# daisy-remote.net
KiCad netlist of a schematic drawn in EAGLE
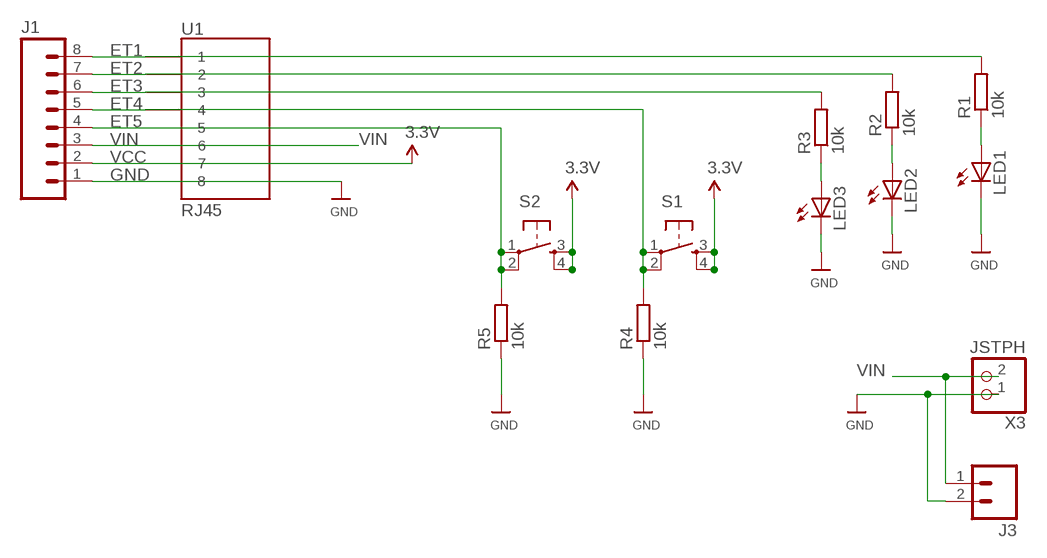
[diagram p0: schematic, sheet 1]

(export (version "E")
  (design (tool "Eeschema 10.0.6"))
  (components
    (comp (ref "J1")
      (value "M08")
      (footprint "eagle-import:1X08_ROUND")
      (libsource (lib "eagle-import") (part "M08"))
    )
    (comp (ref "J3")
      (value "M02PTH")
      (footprint "eagle-import:1X02")
      (libsource (lib "eagle-import") (part "M02PTH"))
    )
    (comp (ref "LED1")
      (value "LED5MM")
      (footprint "eagle-import:LED5MM")
      (libsource (lib "eagle-import") (part "LED5MM"))
    )
    (comp (ref "LED2")
      (value "LED5MM")
      (footprint "eagle-import:LED5MM")
      (libsource (lib "eagle-import") (part "LED5MM"))
    )
    (comp (ref "LED3")
      (value "LED5MM")
      (footprint "eagle-import:LED5MM")
      (libsource (lib "eagle-import") (part "LED5MM"))
    )
    (comp (ref "R1")
      (value "10k")
      (footprint "eagle-import:0204_7")
      (libsource (lib "eagle-import") (part "R-EU_0204/7"))
    )
    (comp (ref "R2")
      (value "10k")
      (footprint "eagle-import:0204_7")
      (libsource (lib "eagle-import") (part "R-EU_0204/7"))
    )
    (comp (ref "R3")
      (value "10k")
      (footprint "eagle-import:0204_7")
      (libsource (lib "eagle-import") (part "R-EU_0204/7"))
    )
    (comp (ref "R4")
      (value "10k")
      (footprint "eagle-import:0204_7")
      (libsource (lib "eagle-import") (part "R-EU_0204/7"))
    )
    (comp (ref "R5")
      (value "10k")
      (footprint "eagle-import:0204_7")
      (libsource (lib "eagle-import") (part "R-EU_0204/7"))
    )
    (comp (ref "S1")
      (value "TAC_SWITCHPTH")
      (footprint "eagle-import:TACTILE-PTH")
      (libsource (lib "eagle-import") (part "TAC_SWITCHPTH"))
    )
    (comp (ref "S2")
      (value "TAC_SWITCHPTH")
      (footprint "eagle-import:TACTILE-PTH")
      (libsource (lib "eagle-import") (part "TAC_SWITCHPTH"))
    )
    (comp (ref "U1")
      (value "RJ45")
      (footprint "eagle-import:RJ45-8")
      (libsource (lib "eagle-import") (part "RJ45-8PTH"))
    )
    (comp (ref "X3")
      (value "JSTPH")
      (footprint "eagle-import:JSTPH2")
      (libsource (lib "eagle-import") (part "CON_JST_PH_2PIN"))
    )
  )
  (nets
    (net (code "1") (name "/ET1") (class "Default")
      (node (ref "J1") (pin "8") (pinfunction "8_8") (pintype "passive"))
      (node (ref "R1") (pin "2") (pinfunction "2_2") (pintype "passive"))
      (node (ref "U1") (pin "1") (pinfunction "1_1") (pintype "bidirectional"))
    )
    (net (code "2") (name "/ET2") (class "Default")
      (node (ref "J1") (pin "7") (pinfunction "7_7") (pintype "passive"))
      (node (ref "R2") (pin "2") (pinfunction "2_2") (pintype "passive"))
      (node (ref "U1") (pin "2") (pinfunction "2_2") (pintype "bidirectional"))
    )
    (net (code "3") (name "/ET3") (class "Default")
      (node (ref "J1") (pin "6") (pinfunction "6_6") (pintype "passive"))
      (node (ref "R3") (pin "2") (pinfunction "2_2") (pintype "passive"))
      (node (ref "U1") (pin "3") (pinfunction "3_3") (pintype "bidirectional"))
    )
    (net (code "4") (name "/ET4") (class "Default")
      (node (ref "J1") (pin "5") (pinfunction "5_5") (pintype "passive"))
      (node (ref "R4") (pin "2") (pinfunction "2_2") (pintype "passive"))
      (node (ref "S1") (pin "1") (pinfunction "1_1") (pintype "passive"))
      (node (ref "S1") (pin "2") (pinfunction "2_2") (pintype "passive"))
      (node (ref "U1") (pin "4") (pinfunction "4_4") (pintype "bidirectional"))
    )
    (net (code "5") (name "/ET5") (class "Default")
      (node (ref "J1") (pin "4") (pinfunction "4_4") (pintype "passive"))
      (node (ref "R5") (pin "2") (pinfunction "2_2") (pintype "passive"))
      (node (ref "S2") (pin "1") (pinfunction "1_1") (pintype "passive"))
      (node (ref "S2") (pin "2") (pinfunction "2_2") (pintype "passive"))
      (node (ref "U1") (pin "5") (pinfunction "5_5") (pintype "bidirectional"))
    )
    (net (code "6") (name "/VIN") (class "Default")
      (node (ref "J1") (pin "3") (pinfunction "3_3") (pintype "passive"))
      (node (ref "J3") (pin "1") (pinfunction "1_1") (pintype "passive"))
      (node (ref "U1") (pin "6") (pinfunction "6_6") (pintype "bidirectional"))
      (node (ref "X3") (pin "2") (pinfunction "2_2") (pintype "passive"))
    )
    (net (code "7") (name "3.3V") (class "Default")
      (node (ref "J1") (pin "2") (pinfunction "2_2") (pintype "passive"))
      (node (ref "S1") (pin "3") (pinfunction "3_3") (pintype "passive"))
      (node (ref "S1") (pin "4") (pinfunction "4_4") (pintype "passive"))
      (node (ref "S2") (pin "3") (pinfunction "3_3") (pintype "passive"))
      (node (ref "S2") (pin "4") (pinfunction "4_4") (pintype "passive"))
      (node (ref "U1") (pin "7") (pinfunction "7_7") (pintype "bidirectional"))
    )
    (net (code "8") (name "GND") (class "Default")
      (node (ref "J1") (pin "1") (pinfunction "1_1") (pintype "passive"))
      (node (ref "J3") (pin "2") (pinfunction "2_2") (pintype "passive"))
      (node (ref "LED1") (pin "K") (pinfunction "C_K") (pintype "passive"))
      (node (ref "LED2") (pin "K") (pinfunction "C_K") (pintype "passive"))
      (node (ref "LED3") (pin "K") (pinfunction "C_K") (pintype "passive"))
      (node (ref "R4") (pin "1") (pinfunction "1_1") (pintype "passive"))
      (node (ref "R5") (pin "1") (pinfunction "1_1") (pintype "passive"))
      (node (ref "U1") (pin "8") (pinfunction "8_8") (pintype "bidirectional"))
      (node (ref "X3") (pin "1") (pinfunction "1_1") (pintype "passive"))
    )
    (net (code "9") (name "Net-(LED1-PadA)") (class "Default")
      (node (ref "LED1") (pin "A") (pinfunction "A_A") (pintype "passive"))
      (node (ref "R1") (pin "1") (pinfunction "1_1") (pintype "passive"))
    )
    (net (code "10") (name "Net-(LED2-PadA)") (class "Default")
      (node (ref "LED2") (pin "A") (pinfunction "A_A") (pintype "passive"))
      (node (ref "R2") (pin "1") (pinfunction "1_1") (pintype "passive"))
    )
    (net (code "11") (name "Net-(LED3-PadA)") (class "Default")
      (node (ref "LED3") (pin "A") (pinfunction "A_A") (pintype "passive"))
      (node (ref "R3") (pin "1") (pinfunction "1_1") (pintype "passive"))
    )
  )
)
